# IsoJTAG.net
KiCad netlist of a schematic drawn in Altium Designer
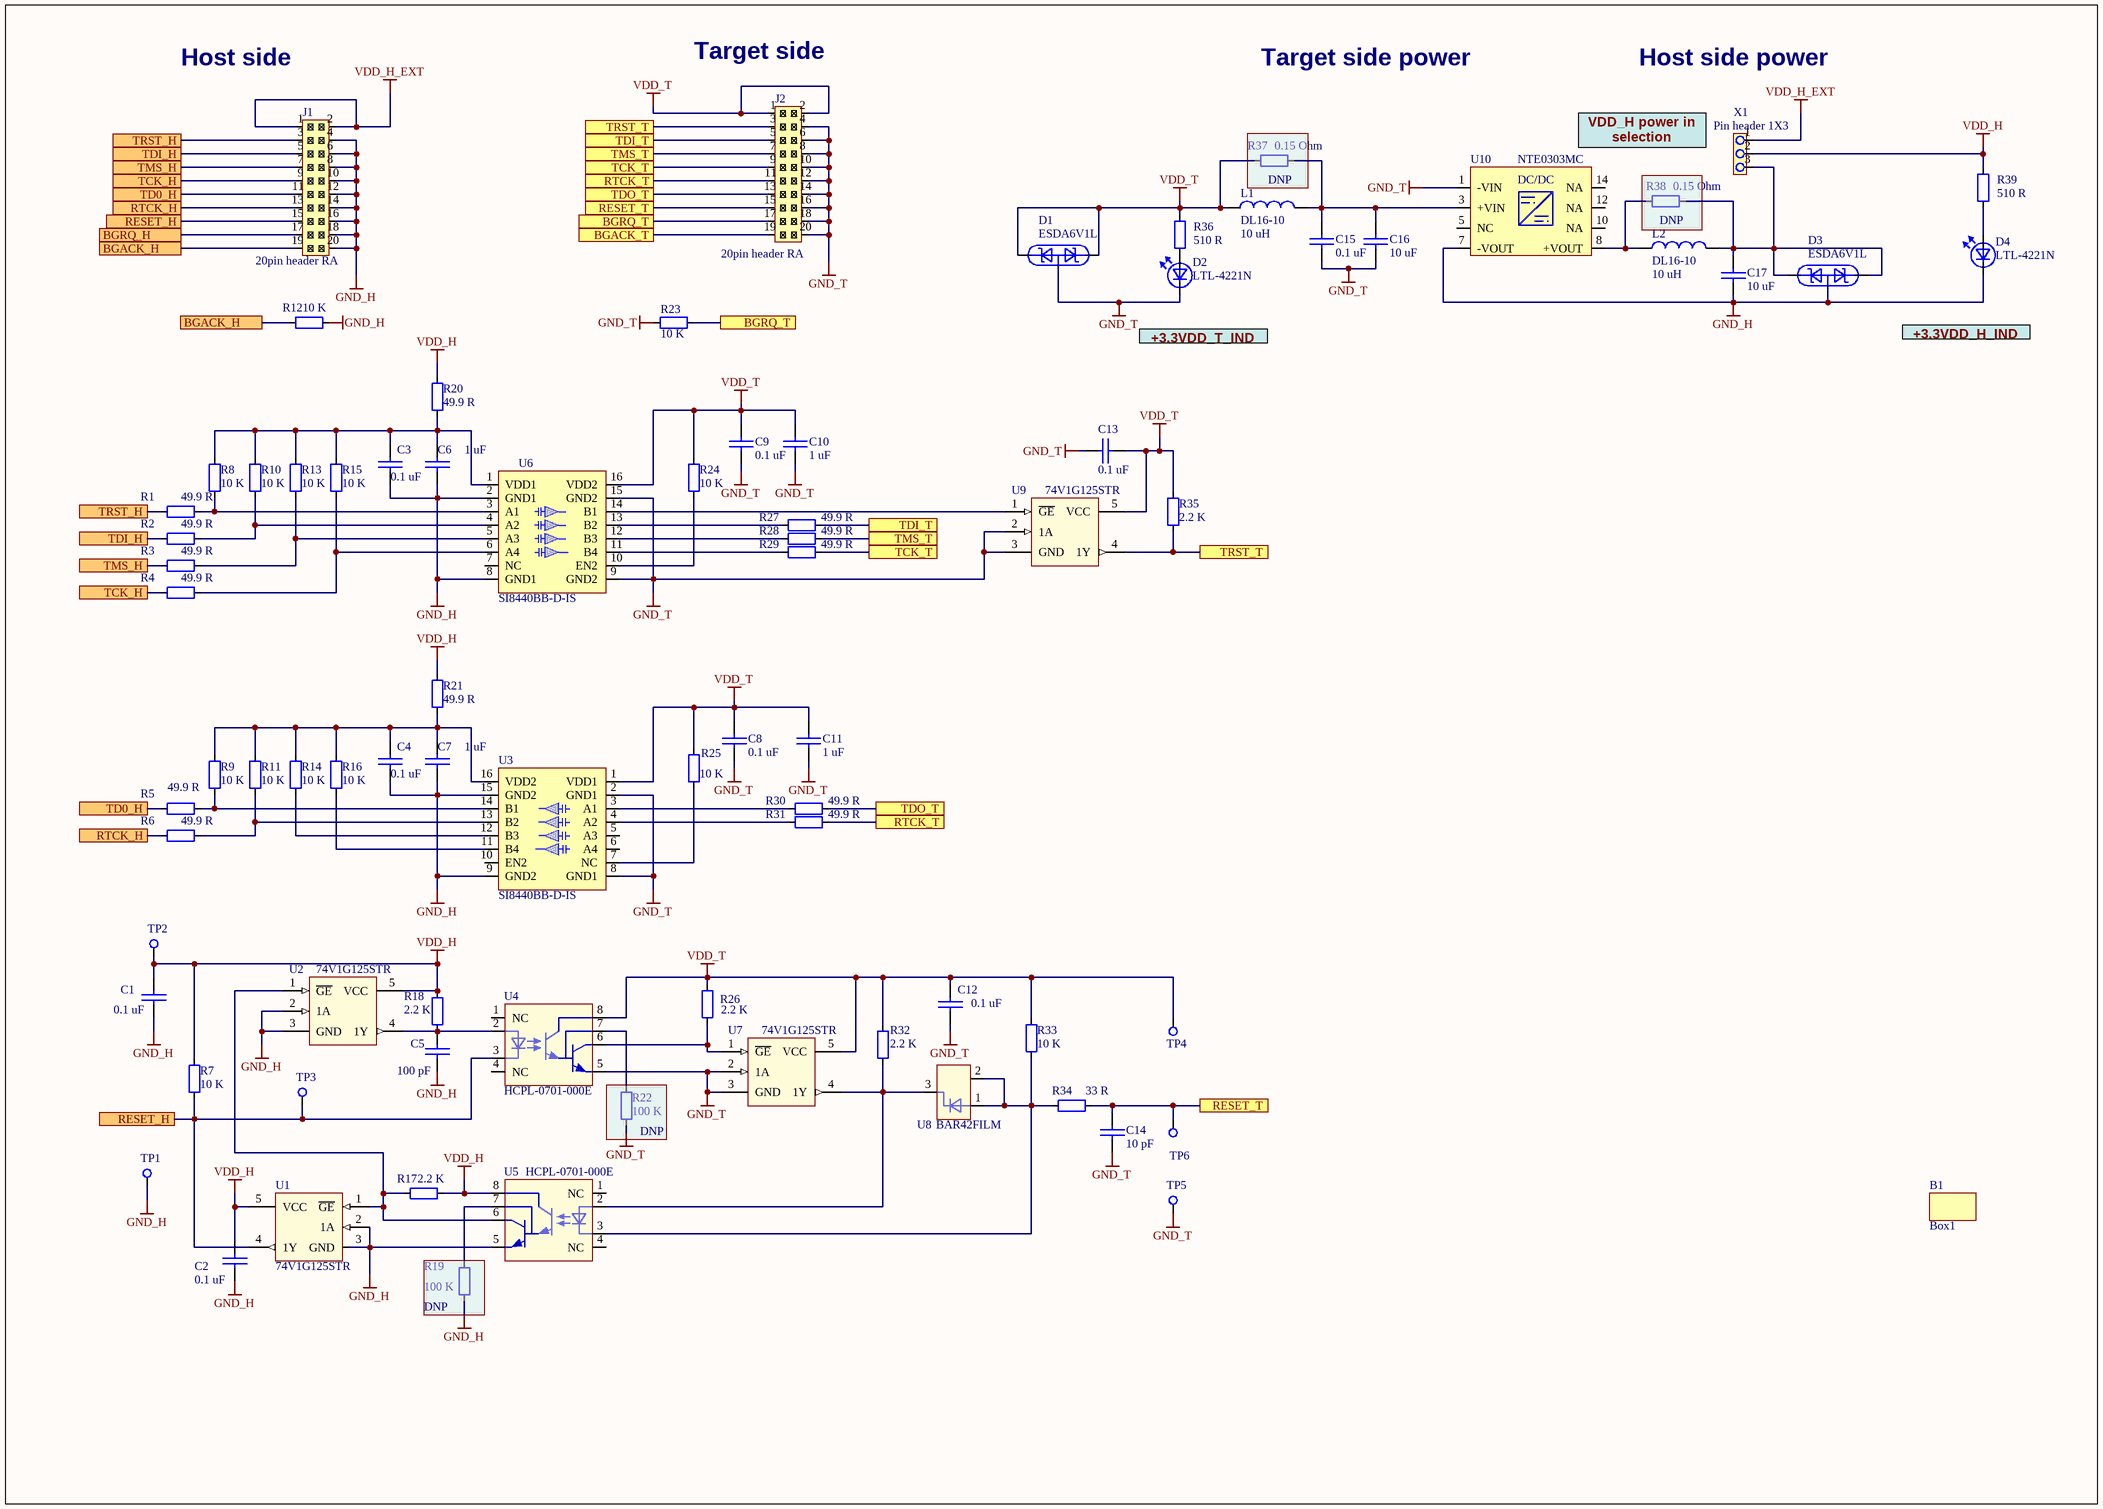
[diagram p0: IsoJTAG.SchDoc]

(export (version "E")
  (design (tool "Eeschema 10.0.6"))
  (components
    (comp (ref "B1")
      (value "Box1")
      (description "Enclosure: multipurpose; 1593; X:66mm; Y:66mm; Z:28mm; ABS; black")
      (fields (field (name "MANUFACTURER") "HAMMOND") (field (name "PARTNUM") "HA1593KBK"))
      (libsource (lib "JTAG_opto") (part "HA1593KBK box"))
    )
    (comp (ref "C1")
      (value "0.1 uF")
      (footprint "2012[0805]")
      (description "0.1 uF, X7R,  0805")
      (fields (field (name "VOLTAGE") "50 V") (field (name "TOLERANCE") "+-10%"))
      (libsource (lib "ea_Capacitors") (part "0805, 0.1 uF, 50 V, X7R"))
    )
    (comp (ref "C2")
      (value "0.1 uF")
      (footprint "2012[0805]")
      (description "0.1 uF, X7R,  0805")
      (fields (field (name "VOLTAGE") "50 V") (field (name "TOLERANCE") "+-10%"))
      (libsource (lib "ea_Capacitors") (part "0805, 0.1 uF, 50 V, X7R"))
    )
    (comp (ref "C3")
      (value "0.1 uF")
      (footprint "2012[0805]")
      (description "0.1 uF, X7R,  0805")
      (fields (field (name "VOLTAGE") "50 V") (field (name "TOLERANCE") "+-10%"))
      (libsource (lib "ea_Capacitors") (part "0805, 0.1 uF, 50 V, X7R"))
    )
    (comp (ref "C4")
      (value "0.1 uF")
      (footprint "2012[0805]")
      (description "0.1 uF, X7R,  0805")
      (fields (field (name "VOLTAGE") "50 V") (field (name "TOLERANCE") "+-10%"))
      (libsource (lib "ea_Capacitors") (part "0805, 0.1 uF, 50 V, X7R"))
    )
    (comp (ref "C5")
      (value "100 pF")
      (footprint "1608[0603]")
      (description "100 pF, 50V, 5%, NP0, 0603 SMD MLC Capacitor")
      (fields (field (name "VOLTAGE") "50 V") (field (name "TOLERANCE") "5%"))
      (libsource (lib "ea_Capacitors") (part "CCPF100K0603"))
    )
    (comp (ref "C6")
      (value "1 uF")
      (footprint "2012[0805]")
      (description "1 uF, 16V, 10%, X7R, 0805")
      (fields (field (name "VOLTAGE") "16 V") (field (name "TOLERANCE") "10%"))
      (libsource (lib "ea_Capacitors") (part "CVUF001K0805"))
    )
    (comp (ref "C7")
      (value "1 uF")
      (footprint "2012[0805]")
      (description "1 uF, 16V, 10%, X7R, 0805")
      (fields (field (name "VOLTAGE") "16 V") (field (name "TOLERANCE") "10%"))
      (libsource (lib "ea_Capacitors") (part "CVUF001K0805"))
    )
    (comp (ref "C8")
      (value "0.1 uF")
      (footprint "2012[0805]")
      (description "0.1 uF, X7R,  0805")
      (fields (field (name "VOLTAGE") "50 V") (field (name "TOLERANCE") "+-10%"))
      (libsource (lib "ea_Capacitors") (part "0805, 0.1 uF, 50 V, X7R"))
    )
    (comp (ref "C9")
      (value "0.1 uF")
      (footprint "2012[0805]")
      (description "0.1 uF, X7R,  0805")
      (fields (field (name "VOLTAGE") "50 V") (field (name "TOLERANCE") "+-10%"))
      (libsource (lib "ea_Capacitors") (part "0805, 0.1 uF, 50 V, X7R"))
    )
    (comp (ref "C10")
      (value "1 uF")
      (footprint "2012[0805]")
      (description "1 uF, 16V, 10%, X7R, 0805")
      (fields (field (name "VOLTAGE") "16 V") (field (name "TOLERANCE") "10%"))
      (libsource (lib "ea_Capacitors") (part "CVUF001K0805"))
    )
    (comp (ref "C11")
      (value "1 uF")
      (footprint "2012[0805]")
      (description "1 uF, 16V, 10%, X7R, 0805")
      (fields (field (name "VOLTAGE") "16 V") (field (name "TOLERANCE") "10%"))
      (libsource (lib "ea_Capacitors") (part "CVUF001K0805"))
    )
    (comp (ref "C12")
      (value "0.1 uF")
      (footprint "2012[0805]")
      (description "0.1 uF, X7R,  0805")
      (fields (field (name "VOLTAGE") "50 V") (field (name "TOLERANCE") "+-10%"))
      (libsource (lib "ea_Capacitors") (part "0805, 0.1 uF, 50 V, X7R"))
    )
    (comp (ref "C13")
      (value "0.1 uF")
      (footprint "2012[0805]")
      (description "0.1 uF, X7R,  0805")
      (fields (field (name "VOLTAGE") "50 V") (field (name "TOLERANCE") "+-10%"))
      (libsource (lib "ea_Capacitors") (part "0805, 0.1 uF, 50 V, X7R"))
    )
    (comp (ref "C14")
      (value "10 pF")
      (footprint "1608[0603]")
      (description "10 pF, 50V, 5%, NP0, 0603 SMD MLC Capacitor")
      (fields (field (name "VOLTAGE") "50 V") (field (name "TOLERANCE") "5%"))
      (libsource (lib "ea_Capacitors") (part "CCPF010K0603"))
    )
    (comp (ref "C15")
      (value "0.1 uF")
      (footprint "2012[0805]")
      (description "0.1 uF, X7R,  0805")
      (fields (field (name "VOLTAGE") "50 V") (field (name "TOLERANCE") "+-10%"))
      (libsource (lib "ea_Capacitors") (part "0805, 0.1 uF, 50 V, X7R"))
    )
    (comp (ref "C16")
      (value "10 uF")
      (footprint "2012[0805]")
      (description "10 uF, 10V, X5R, 10%, 0805,  -55°C..85°C")
      (fields (field (name "VOLTAGE") "10V") (field (name "TOLERANCE") "10%"))
      (libsource (lib "ea_Capacitors") (part "GRM21BR61A106KE19L"))
    )
    (comp (ref "C17")
      (value "10 uF")
      (footprint "2012[0805]")
      (description "10 uF, 10V, X5R, 10%, 0805,  -55°C..85°C")
      (fields (field (name "VOLTAGE") "10V") (field (name "TOLERANCE") "10%"))
      (libsource (lib "ea_Capacitors") (part "GRM21BR61A106KE19L"))
    )
    (comp (ref "D1")
      (value "ESDA6V1L")
      (footprint "SOT23")
      (description "Dual transil array for ESD, 6.1 V, 300 W")
      (fields (field (name "MANUFACTURER") "Micro Commercial Co") (field (name "PARTNUM") "ESDA6V1L-TPCT-ND"))
      (libsource (lib "*") (part "ESDA6V1L"))
    )
    (comp (ref "D2")
      (value "LTL-4221N")
      (footprint "LED 3 mm")
      (description "LED 3 mm")
      (libsource (lib "ea_Indicators") (part "LTL-4221N"))
    )
    (comp (ref "D3")
      (value "ESDA6V1L")
      (footprint "SOT23")
      (description "Dual transil array for ESD, 6.1 V, 300 W")
      (fields (field (name "MANUFACTURER") "Micro Commercial Co") (field (name "PARTNUM") "ESDA6V1L-TPCT-ND"))
      (libsource (lib "*") (part "ESDA6V1L"))
    )
    (comp (ref "D4")
      (value "LTL-4221N")
      (footprint "LED 3 mm")
      (description "LED 3 mm")
      (libsource (lib "ea_Indicators") (part "LTL-4221N"))
    )
    (comp (ref "J1")
      (value "20pin header RA")
      (footprint "918520x323")
      (description "Socket; IDC; male; PIN:20; angled; THT; 1.27mm; Pitch:2.54mm")
      (fields (field (name "MANUFACTURER") "Harting") (field (name "PARTNUM") "2-1634689-0"))
      (libsource (lib "JTAG_opto") (part "2-1634689-0 20pin header"))
    )
    (comp (ref "J2")
      (value "20pin header RA")
      (footprint "918520x323")
      (description "Socket; IDC; male; PIN:20; angled; THT; 1.27mm; Pitch:2.54mm")
      (fields (field (name "MANUFACTURER") "Harting") (field (name "PARTNUM") "2-1634689-0"))
      (libsource (lib "JTAG_opto") (part "2-1634689-0 20pin header"))
    )
    (comp (ref "L1")
      (value "DL16-10")
      (footprint "DL16-10")
      (description "Inductor: wire; 10uH; Ioper:1.1A; 0.16R; SMD; Isat:1.1A; B:4.45mm")
      (fields
        (field (name "MANUFACTURER") "FERROCORE")
        (field (name "TOLERANCE") "20%")
        (field (name "ALTIUM_VALUE") "10 uH")
      )
      (libsource (lib "JTAG_opto") (part "DL16-10 10uH"))
    )
    (comp (ref "L2")
      (value "DL16-10")
      (footprint "DL16-10")
      (description "Inductor: wire; 10uH; Ioper:1.1A; 0.16R; SMD; Isat:1.1A; B:4.45mm")
      (fields
        (field (name "MANUFACTURER") "FERROCORE")
        (field (name "TOLERANCE") "20%")
        (field (name "ALTIUM_VALUE") "10 uH")
      )
      (libsource (lib "JTAG_opto") (part "DL16-10 10uH"))
    )
    (comp (ref "R1")
      (value "49.9 R")
      (footprint "0603")
      (description "49.9 R, 1%, 0.1 W, 0603, SMD Resistor, Taped")
      (fields (field (name "MANUFACTURER") "Vishay/Dale") (field (name "TOLERANCE") "1%"))
      (libsource (lib "ea_Resistors") (part "CRCW060349R9FKEA"))
    )
    (comp (ref "R2")
      (value "49.9 R")
      (footprint "0603")
      (description "49.9 R, 1%, 0.1 W, 0603, SMD Resistor, Taped")
      (fields (field (name "MANUFACTURER") "Vishay/Dale") (field (name "TOLERANCE") "1%"))
      (libsource (lib "ea_Resistors") (part "CRCW060349R9FKEA"))
    )
    (comp (ref "R3")
      (value "49.9 R")
      (footprint "0603")
      (description "49.9 R, 1%, 0.1 W, 0603, SMD Resistor, Taped")
      (fields (field (name "MANUFACTURER") "Vishay/Dale") (field (name "TOLERANCE") "1%"))
      (libsource (lib "ea_Resistors") (part "CRCW060349R9FKEA"))
    )
    (comp (ref "R4")
      (value "49.9 R")
      (footprint "0603")
      (description "49.9 R, 1%, 0.1 W, 0603, SMD Resistor, Taped")
      (fields (field (name "MANUFACTURER") "Vishay/Dale") (field (name "TOLERANCE") "1%"))
      (libsource (lib "ea_Resistors") (part "CRCW060349R9FKEA"))
    )
    (comp (ref "R5")
      (value "49.9 R")
      (footprint "0603")
      (description "49.9 R, 1%, 0.1 W, 0603, SMD Resistor, Taped")
      (fields (field (name "MANUFACTURER") "Vishay/Dale") (field (name "TOLERANCE") "1%"))
      (libsource (lib "ea_Resistors") (part "CRCW060349R9FKEA"))
    )
    (comp (ref "R6")
      (value "49.9 R")
      (footprint "0603")
      (description "49.9 R, 1%, 0.1 W, 0603, SMD Resistor, Taped")
      (fields (field (name "MANUFACTURER") "Vishay/Dale") (field (name "TOLERANCE") "1%"))
      (libsource (lib "ea_Resistors") (part "CRCW060349R9FKEA"))
    )
    (comp (ref "R7")
      (value "10 K")
      (footprint "0603")
      (description "10 K, 1%, 0603, SMD Resistor, Taped")
      (fields (field (name "MANUFACTURER") "Vishay") (field (name "TOLERANCE") "1%"))
      (libsource (lib "ea_Resistors") (part "RL0603K010-1"))
    )
    (comp (ref "R8")
      (value "10 K")
      (footprint "0603")
      (description "10 K, 1%, 0603, SMD Resistor, Taped")
      (fields (field (name "MANUFACTURER") "Vishay") (field (name "TOLERANCE") "1%"))
      (libsource (lib "ea_Resistors") (part "RL0603K010-1"))
    )
    (comp (ref "R9")
      (value "10 K")
      (footprint "0603")
      (description "10 K, 1%, 0603, SMD Resistor, Taped")
      (fields (field (name "MANUFACTURER") "Vishay") (field (name "TOLERANCE") "1%"))
      (libsource (lib "ea_Resistors") (part "RL0603K010-1"))
    )
    (comp (ref "R10")
      (value "10 K")
      (footprint "0603")
      (description "10 K, 1%, 0603, SMD Resistor, Taped")
      (fields (field (name "MANUFACTURER") "Vishay") (field (name "TOLERANCE") "1%"))
      (libsource (lib "ea_Resistors") (part "RL0603K010-1"))
    )
    (comp (ref "R11")
      (value "10 K")
      (footprint "0603")
      (description "10 K, 1%, 0603, SMD Resistor, Taped")
      (fields (field (name "MANUFACTURER") "Vishay") (field (name "TOLERANCE") "1%"))
      (libsource (lib "ea_Resistors") (part "RL0603K010-1"))
    )
    (comp (ref "R12")
      (value "10 K")
      (footprint "0603")
      (description "10 K, 1%, 0603, SMD Resistor, Taped")
      (fields (field (name "MANUFACTURER") "Vishay") (field (name "TOLERANCE") "1%"))
      (libsource (lib "") (part "RL0603K010-1_1"))
    )
    (comp (ref "R13")
      (value "10 K")
      (footprint "0603")
      (description "10 K, 1%, 0603, SMD Resistor, Taped")
      (fields (field (name "MANUFACTURER") "Vishay") (field (name "TOLERANCE") "1%"))
      (libsource (lib "ea_Resistors") (part "RL0603K010-1"))
    )
    (comp (ref "R14")
      (value "10 K")
      (footprint "0603")
      (description "10 K, 1%, 0603, SMD Resistor, Taped")
      (fields (field (name "MANUFACTURER") "Vishay") (field (name "TOLERANCE") "1%"))
      (libsource (lib "ea_Resistors") (part "RL0603K010-1"))
    )
    (comp (ref "R15")
      (value "10 K")
      (footprint "0603")
      (description "10 K, 1%, 0603, SMD Resistor, Taped")
      (fields (field (name "MANUFACTURER") "Vishay") (field (name "TOLERANCE") "1%"))
      (libsource (lib "ea_Resistors") (part "RL0603K010-1"))
    )
    (comp (ref "R16")
      (value "10 K")
      (footprint "0603")
      (description "10 K, 1%, 0603, SMD Resistor, Taped")
      (fields (field (name "MANUFACTURER") "Vishay") (field (name "TOLERANCE") "1%"))
      (libsource (lib "ea_Resistors") (part "RL0603K010-1"))
    )
    (comp (ref "R17")
      (value "2.2 K")
      (footprint "0603")
      (description "2.2 K, 1%, 0603, SMD Resistor, Taped")
      (fields (field (name "MANUFACTURER") "Vishay") (field (name "TOLERANCE") "1%"))
      (libsource (lib "") (part "RL0603K002.2-1_1"))
    )
    (comp (ref "R18")
      (value "2.2 K")
      (footprint "0603")
      (description "2.2 K, 1%, 0603, SMD Resistor, Taped")
      (fields (field (name "MANUFACTURER") "Vishay") (field (name "TOLERANCE") "1%"))
      (libsource (lib "ea_Resistors") (part "RL0603K002.2-1"))
    )
    (comp (ref "R19")
      (value "100 K")
      (footprint "0603")
      (description "100 K, 1%, 0603, SMD Resistor, Taped")
      (fields (field (name "MANUFACTURER") "Vishay") (field (name "TOLERANCE") "1%"))
      (libsource (lib "ea_Resistors") (part "RL0603K100-1"))
    )
    (comp (ref "R20")
      (value "49.9 R")
      (footprint "0603")
      (description "49.9 R, 1%, 0.1 W, 0603, SMD Resistor, Taped")
      (fields (field (name "MANUFACTURER") "Vishay/Dale") (field (name "TOLERANCE") "1%"))
      (libsource (lib "") (part "CRCW060349R9FKEA_1"))
    )
    (comp (ref "R21")
      (value "49.9 R")
      (footprint "0603")
      (description "49.9 R, 1%, 0.1 W, 0603, SMD Resistor, Taped")
      (fields (field (name "MANUFACTURER") "Vishay/Dale") (field (name "TOLERANCE") "1%"))
      (libsource (lib "") (part "CRCW060349R9FKEA_1"))
    )
    (comp (ref "R22")
      (value "100 K")
      (footprint "0603")
      (description "100 K, 1%, 0603, SMD Resistor, Taped")
      (fields (field (name "MANUFACTURER") "Vishay") (field (name "TOLERANCE") "1%"))
      (libsource (lib "") (part "RL0603K100-1_1"))
    )
    (comp (ref "R23")
      (value "10 K")
      (footprint "0603")
      (description "10 K, 1%, 0603, SMD Resistor, Taped")
      (fields (field (name "MANUFACTURER") "Vishay") (field (name "TOLERANCE") "1%"))
      (libsource (lib "ea_Resistors") (part "RL0603K010-1"))
    )
    (comp (ref "R24")
      (value "10 K")
      (footprint "0603")
      (description "10 K, 1%, 0603, SMD Resistor, Taped")
      (fields (field (name "MANUFACTURER") "Vishay") (field (name "TOLERANCE") "1%"))
      (libsource (lib "") (part "RL0603K010-1_2"))
    )
    (comp (ref "R25")
      (value "10 K")
      (footprint "0603")
      (description "10 K, 1%, 0603, SMD Resistor, Taped")
      (fields (field (name "MANUFACTURER") "Vishay") (field (name "TOLERANCE") "1%"))
      (libsource (lib "") (part "RL0603K010-1_2"))
    )
    (comp (ref "R26")
      (value "2.2 K")
      (footprint "0603")
      (description "2.2 K, 1%, 0603, SMD Resistor, Taped")
      (fields (field (name "MANUFACTURER") "Vishay") (field (name "TOLERANCE") "1%"))
      (libsource (lib "ea_Resistors") (part "RL0603K002.2-1"))
    )
    (comp (ref "R27")
      (value "49.9 R")
      (footprint "0603")
      (description "49.9 R, 1%, 0.1 W, 0603, SMD Resistor, Taped")
      (fields (field (name "MANUFACTURER") "Vishay/Dale") (field (name "TOLERANCE") "1%"))
      (libsource (lib "ea_Resistors") (part "CRCW060349R9FKEA"))
    )
    (comp (ref "R28")
      (value "49.9 R")
      (footprint "0603")
      (description "49.9 R, 1%, 0.1 W, 0603, SMD Resistor, Taped")
      (fields (field (name "MANUFACTURER") "Vishay/Dale") (field (name "TOLERANCE") "1%"))
      (libsource (lib "ea_Resistors") (part "CRCW060349R9FKEA"))
    )
    (comp (ref "R29")
      (value "49.9 R")
      (footprint "0603")
      (description "49.9 R, 1%, 0.1 W, 0603, SMD Resistor, Taped")
      (fields (field (name "MANUFACTURER") "Vishay/Dale") (field (name "TOLERANCE") "1%"))
      (libsource (lib "ea_Resistors") (part "CRCW060349R9FKEA"))
    )
    (comp (ref "R30")
      (value "49.9 R")
      (footprint "0603")
      (description "49.9 R, 1%, 0.1 W, 0603, SMD Resistor, Taped")
      (fields (field (name "MANUFACTURER") "Vishay/Dale") (field (name "TOLERANCE") "1%"))
      (libsource (lib "ea_Resistors") (part "CRCW060349R9FKEA"))
    )
    (comp (ref "R31")
      (value "49.9 R")
      (footprint "0603")
      (description "49.9 R, 1%, 0.1 W, 0603, SMD Resistor, Taped")
      (fields (field (name "MANUFACTURER") "Vishay/Dale") (field (name "TOLERANCE") "1%"))
      (libsource (lib "ea_Resistors") (part "CRCW060349R9FKEA"))
    )
    (comp (ref "R32")
      (value "2.2 K")
      (footprint "0603")
      (description "2.2 K, 1%, 0603, SMD Resistor, Taped")
      (fields (field (name "MANUFACTURER") "Vishay") (field (name "TOLERANCE") "1%"))
      (libsource (lib "ea_Resistors") (part "RL0603K002.2-1"))
    )
    (comp (ref "R33")
      (value "10 K")
      (footprint "0603")
      (description "10 K, 1%, 0603, SMD Resistor, Taped")
      (fields (field (name "MANUFACTURER") "Vishay") (field (name "TOLERANCE") "1%"))
      (libsource (lib "ea_Resistors") (part "RL0603K010-1"))
    )
    (comp (ref "R34")
      (value "33 R")
      (footprint "0603")
      (description "33 R, 1%, 0603, SMD Resistor, Taped")
      (fields (field (name "MANUFACTURER") "Vishay") (field (name "TOLERANCE") "1%"))
      (libsource (lib "ea_Resistors") (part "RL0603E033-1"))
    )
    (comp (ref "R35")
      (value "2.2 K")
      (footprint "0603")
      (description "2.2 K, 1%, 0603, SMD Resistor, Taped")
      (fields (field (name "MANUFACTURER") "Vishay") (field (name "TOLERANCE") "1%"))
      (libsource (lib "ea_Resistors") (part "RL0603K002.2-1"))
    )
    (comp (ref "R36")
      (value "510 R")
      (footprint "0603")
      (description "510 R, 1%, 0603, SMD Resistor, Taped")
      (fields (field (name "MANUFACTURER") "Vishay") (field (name "TOLERANCE") "1%"))
      (libsource (lib "ea_Resistors") (part "RL0603E510-1"))
    )
    (comp (ref "R37")
      (value "0.15 Ohm")
      (footprint "3216[1206]")
      (description "0.15 Ohm, 0.25 W, 1% 1206")
      (fields (field (name "MANUFACTURER") "Panasonic") (field (name "TOLERANCE") "1%"))
      (libsource (lib "ea_Resistors") (part "ERJ-8RSFR15V"))
    )
    (comp (ref "R38")
      (value "0.15 Ohm")
      (footprint "3216[1206]")
      (description "0.15 Ohm, 0.25 W, 1% 1206")
      (fields (field (name "MANUFACTURER") "Panasonic") (field (name "TOLERANCE") "1%"))
      (libsource (lib "ea_Resistors") (part "ERJ-8RSFR15V"))
    )
    (comp (ref "R39")
      (value "510 R")
      (footprint "0603")
      (description "510 R, 1%, 0603, SMD Resistor, Taped")
      (fields (field (name "MANUFACTURER") "Vishay") (field (name "TOLERANCE") "1%"))
      (libsource (lib "ea_Resistors") (part "RL0603E510-1"))
    )
    (comp (ref "TP1")
      (value "TP 0.4-0.8")
      (footprint "TP 0.4-0.8")
      (libsource (lib "ea_Mechanical") (part "TP 0.4-0.8"))
    )
    (comp (ref "TP2")
      (value "TP 0.4-0.8")
      (footprint "TP 0.4-0.8")
      (libsource (lib "ea_Mechanical") (part "TP 0.4-0.8"))
    )
    (comp (ref "TP3")
      (value "TP 0.4-0.8")
      (footprint "TP 0.4-0.8")
      (libsource (lib "ea_Mechanical") (part "TP 0.4-0.8"))
    )
    (comp (ref "TP4")
      (value "TP 0.4-0.8")
      (footprint "TP 0.4-0.8")
      (libsource (lib "ea_Mechanical") (part "TP 0.4-0.8"))
    )
    (comp (ref "TP5")
      (value "TP 0.4-0.8")
      (footprint "TP 0.4-0.8")
      (libsource (lib "ea_Mechanical") (part "TP 0.4-0.8"))
    )
    (comp (ref "TP6")
      (value "TP 0.4-0.8")
      (footprint "TP 0.4-0.8")
      (libsource (lib "ea_Mechanical") (part "TP 0.4-0.8"))
    )
    (comp (ref "U1")
      (value "74V1G125STR")
      (footprint "SOT23-5L")
      (description "Single Bus Buffer (3-State), Non Inverting, 2-5.5V, SOT-23-5, -55-125C,")
      (fields (field (name "MANUFACTURER") "ST"))
      (libsource (lib "") (part "74V1G125STR buffer_1"))
    )
    (comp (ref "U2")
      (value "74V1G125STR")
      (footprint "SOT23-5L")
      (description "Single Bus Buffer (3-State), Non Inverting, 2-5.5V, SOT-23-5, -55-125C,")
      (fields (field (name "MANUFACTURER") "ST"))
      (libsource (lib "ea_IC_registers_buffers") (part "74V1G125STR buffer"))
    )
    (comp (ref "U3")
      (value "SI8440BB-D-IS")
      (footprint "SO-G16/D10.4")
      (description "IC ISOLATOR 4CH 5.5V 16-SOIC")
      (fields
        (field (name "MANUFACTURER") "Silicon Laboratories Inc")
        (field (name "PARTNUM") "336-1760-5-ND")
      )
      (libsource (lib "") (part "SI8440AB-D-IS_1"))
    )
    (comp (ref "U4")
      (value "HCPL-0701-000E")
      (footprint "SO-8")
      (description "OPTOCOUPLER, SMD, TRANSISTOR O/P")
      (fields (field (name "MANUFACTURER") "Avago"))
      (libsource (lib "ea_Opto") (part "HCPL-0701-000E"))
    )
    (comp (ref "U5")
      (value "HCPL-0701-000E")
      (footprint "SO-8")
      (description "OPTOCOUPLER, SMD, TRANSISTOR O/P")
      (fields (field (name "MANUFACTURER") "Avago"))
      (libsource (lib "") (part "HCPL-0701-000E_1"))
    )
    (comp (ref "U6")
      (value "SI8440BB-D-IS")
      (footprint "SO-G16/D10.4")
      (description "IC ISOLATOR 4CH 5.5V 16-SOIC")
      (fields
        (field (name "MANUFACTURER") "Silicon Laboratories Inc")
        (field (name "PARTNUM") "336-1760-5-ND")
      )
      (libsource (lib "ea_IC_Interfaces") (part "SI8440AB-D-IS"))
    )
    (comp (ref "U7")
      (value "74V1G125STR")
      (footprint "SOT23-5L")
      (description "Single Bus Buffer (3-State), Non Inverting, 2-5.5V, SOT-23-5, -55-125C,")
      (fields (field (name "MANUFACTURER") "ST"))
      (libsource (lib "ea_IC_registers_buffers") (part "74V1G125STR buffer"))
    )
    (comp (ref "U8")
      (value "BAR42FILM")
      (footprint "SOT23")
      (description "Schottky Single 30V, 100 mA, 400mV, SOT-23, Marking D94")
      (fields (field (name "MANUFACTURER") "ST"))
      (libsource (lib "ea_Diodes") (part "BAR42FILM"))
    )
    (comp (ref "U9")
      (value "74V1G125STR")
      (footprint "SOT23-5L")
      (description "Single Bus Buffer (3-State), Non Inverting, 2-5.5V, SOT-23-5, -55-125C,")
      (fields (field (name "MANUFACTURER") "ST"))
      (libsource (lib "ea_IC_registers_buffers") (part "74V1G125STR buffer"))
    )
    (comp (ref "U10")
      (value "NTE0303MC")
      (footprint "NTE DC_DC")
      (description "CONVERTER, DC/DC, SMD, 1W, 3.3V,  12,7x6.6x7.7mm, 1kV isol")
      (fields (field (name "MANUFACTURER") "MURATA"))
      (libsource (lib "JTAG_opto") (part "NTE0303MC DC/DC"))
    )
    (comp (ref "X1")
      (value "Pin header 1X3")
      (footprint "HDR1X3")
      (libsource (lib "ea_Connectors") (part "Pin header 1X3"))
    )
  )
  (nets
    (net (code "1") (name "/BGACK_H") (class "Default")
      (node (ref "J1") (pin "19") (pinfunction "19_19") (pintype "passive"))
      (node (ref "R12") (pin "2") (pinfunction "2_2") (pintype "passive"))
    )
    (net (code "2") (name "/BGACK_T") (class "Default")
      (node (ref "J2") (pin "19") (pinfunction "19_19") (pintype "passive"))
    )
    (net (code "3") (name "/BGRQ_H") (class "Default")
      (node (ref "J1") (pin "17") (pinfunction "17_17") (pintype "passive"))
    )
    (net (code "4") (name "/BGRQ_T") (class "Default")
      (node (ref "J2") (pin "17") (pinfunction "17_17") (pintype "passive"))
      (node (ref "R23") (pin "2") (pinfunction "2_2") (pintype "passive"))
    )
    (net (code "5") (name "/RESET_H") (class "Default")
      (node (ref "J1") (pin "15") (pinfunction "15_15") (pintype "passive"))
      (node (ref "R7") (pin "1") (pinfunction "1_1") (pintype "passive"))
      (node (ref "TP3") (pin "1") (pinfunction "1_1") (pintype "passive"))
      (node (ref "U1") (pin "4") (pinfunction "1Y_4") (pintype "output"))
      (node (ref "U4") (pin "3") (pinfunction "C_3") (pintype "passive"))
    )
    (net (code "6") (name "/RESET_T") (class "Default")
      (node (ref "C14") (pin "1") (pinfunction "1_1") (pintype "passive"))
      (node (ref "J2") (pin "15") (pinfunction "15_15") (pintype "passive"))
      (node (ref "R34") (pin "1") (pinfunction "1_1") (pintype "passive"))
      (node (ref "TP6") (pin "1") (pinfunction "1_1") (pintype "passive"))
    )
    (net (code "7") (name "/RTCK_H") (class "Default")
      (node (ref "J1") (pin "13") (pinfunction "13_13") (pintype "passive"))
      (node (ref "R6") (pin "2") (pinfunction "2_2") (pintype "passive"))
    )
    (net (code "8") (name "/RTCK_T") (class "Default")
      (node (ref "J2") (pin "11") (pinfunction "11_11") (pintype "passive"))
      (node (ref "R31") (pin "1") (pinfunction "1_1") (pintype "passive"))
    )
    (net (code "9") (name "/TCK_H") (class "Default")
      (node (ref "J1") (pin "9") (pinfunction "9_9") (pintype "passive"))
      (node (ref "R4") (pin "2") (pinfunction "2_2") (pintype "passive"))
    )
    (net (code "10") (name "/TCK_T") (class "Default")
      (node (ref "J2") (pin "9") (pinfunction "9_9") (pintype "passive"))
      (node (ref "R29") (pin "1") (pinfunction "1_1") (pintype "passive"))
    )
    (net (code "11") (name "/TD0_H") (class "Default")
      (node (ref "J1") (pin "11") (pinfunction "11_11") (pintype "passive"))
      (node (ref "R5") (pin "2") (pinfunction "2_2") (pintype "passive"))
    )
    (net (code "12") (name "/TDI_H") (class "Default")
      (node (ref "J1") (pin "5") (pinfunction "5_5") (pintype "passive"))
      (node (ref "R2") (pin "2") (pinfunction "2_2") (pintype "passive"))
    )
    (net (code "13") (name "/TDI_T") (class "Default")
      (node (ref "J2") (pin "5") (pinfunction "5_5") (pintype "passive"))
      (node (ref "R27") (pin "1") (pinfunction "1_1") (pintype "passive"))
    )
    (net (code "14") (name "/TDO_T") (class "Default")
      (node (ref "J2") (pin "13") (pinfunction "13_13") (pintype "passive"))
      (node (ref "R30") (pin "1") (pinfunction "1_1") (pintype "passive"))
    )
    (net (code "15") (name "/TMS_H") (class "Default")
      (node (ref "J1") (pin "7") (pinfunction "7_7") (pintype "passive"))
      (node (ref "R3") (pin "2") (pinfunction "2_2") (pintype "passive"))
    )
    (net (code "16") (name "/TMS_T") (class "Default")
      (node (ref "J2") (pin "7") (pinfunction "7_7") (pintype "passive"))
      (node (ref "R28") (pin "1") (pinfunction "1_1") (pintype "passive"))
    )
    (net (code "17") (name "/TRST_H") (class "Default")
      (node (ref "J1") (pin "3") (pinfunction "3_3") (pintype "passive"))
      (node (ref "R1") (pin "2") (pinfunction "2_2") (pintype "passive"))
    )
    (net (code "18") (name "/TRST_T") (class "Default")
      (node (ref "J2") (pin "3") (pinfunction "3_3") (pintype "passive"))
      (node (ref "R35") (pin "1") (pinfunction "1_1") (pintype "passive"))
      (node (ref "U9") (pin "4") (pinfunction "1Y_4") (pintype "output"))
    )
    (net (code "19") (name "GND_H") (class "Default")
      (node (ref "C1") (pin "2") (pinfunction "2_2") (pintype "passive"))
      (node (ref "C17") (pin "2") (pinfunction "2_2") (pintype "passive"))
      (node (ref "C2") (pin "2") (pinfunction "2_2") (pintype "passive"))
      (node (ref "C3") (pin "1") (pinfunction "1_1") (pintype "passive"))
      (node (ref "C4") (pin "1") (pinfunction "1_1") (pintype "passive"))
      (node (ref "C5") (pin "2") (pinfunction "2_2") (pintype "passive"))
      (node (ref "C6") (pin "2") (pinfunction "2_2") (pintype "passive"))
      (node (ref "C7") (pin "2") (pinfunction "2_2") (pintype "passive"))
      (node (ref "D3") (pin "3") (pintype "passive"))
      (node (ref "D4") (pin "1") (pinfunction "C_1") (pintype "passive"))
      (node (ref "J1") (pin "10") (pinfunction "10_10") (pintype "passive"))
      (node (ref "J1") (pin "12") (pinfunction "12_12") (pintype "passive"))
      (node (ref "J1") (pin "14") (pinfunction "14_14") (pintype "passive"))
      (node (ref "J1") (pin "16") (pinfunction "16_16") (pintype "passive"))
      (node (ref "J1") (pin "18") (pinfunction "18_18") (pintype "passive"))
      (node (ref "J1") (pin "20") (pinfunction "20_20") (pintype "passive"))
      (node (ref "J1") (pin "4") (pinfunction "4_4") (pintype "passive"))
      (node (ref "J1") (pin "6") (pinfunction "6_6") (pintype "passive"))
      (node (ref "J1") (pin "8") (pinfunction "8_8") (pintype "passive"))
      (node (ref "R12") (pin "1") (pinfunction "1_1") (pintype "passive"))
      (node (ref "R19") (pin "2") (pinfunction "2_2") (pintype "passive"))
      (node (ref "TP1") (pin "1") (pinfunction "1_1") (pintype "passive"))
      (node (ref "U1") (pin "2") (pinfunction "1A_2") (pintype "input"))
      (node (ref "U1") (pin "3") (pinfunction "GND_3") (pintype "passive"))
      (node (ref "U10") (pin "7") (pinfunction "-VOUT_7") (pintype "passive"))
      (node (ref "U2") (pin "2") (pinfunction "1A_2") (pintype "input"))
      (node (ref "U2") (pin "3") (pinfunction "GND_3") (pintype "passive"))
      (node (ref "U3") (pin "15") (pinfunction "GND2_15") (pintype "passive"))
      (node (ref "U3") (pin "9") (pinfunction "GND2_9") (pintype "passive"))
      (node (ref "U5") (pin "5") (pinfunction "C_5") (pintype "passive"))
      (node (ref "U6") (pin "2") (pinfunction "GND1_2") (pintype "passive"))
      (node (ref "U6") (pin "8") (pinfunction "GND1_8") (pintype "passive"))
    )
    (net (code "20") (name "GND_T") (class "Default")
      (node (ref "C10") (pin "2") (pinfunction "2_2") (pintype "passive"))
      (node (ref "C11") (pin "2") (pinfunction "2_2") (pintype "passive"))
      (node (ref "C12") (pin "2") (pinfunction "2_2") (pintype "passive"))
      (node (ref "C13") (pin "1") (pinfunction "1_1") (pintype "passive"))
      (node (ref "C14") (pin "2") (pinfunction "2_2") (pintype "passive"))
      (node (ref "C15") (pin "1") (pinfunction "1_1") (pintype "passive"))
      (node (ref "C16") (pin "1") (pinfunction "1_1") (pintype "passive"))
      (node (ref "C8") (pin "1") (pinfunction "1_1") (pintype "passive"))
      (node (ref "C9") (pin "1") (pinfunction "1_1") (pintype "passive"))
      (node (ref "D1") (pin "3") (pintype "passive"))
      (node (ref "D2") (pin "1") (pinfunction "C_1") (pintype "passive"))
      (node (ref "J2") (pin "10") (pinfunction "10_10") (pintype "passive"))
      (node (ref "J2") (pin "12") (pinfunction "12_12") (pintype "passive"))
      (node (ref "J2") (pin "14") (pinfunction "14_14") (pintype "passive"))
      (node (ref "J2") (pin "16") (pinfunction "16_16") (pintype "passive"))
      (node (ref "J2") (pin "18") (pinfunction "18_18") (pintype "passive"))
      (node (ref "J2") (pin "20") (pinfunction "20_20") (pintype "passive"))
      (node (ref "J2") (pin "4") (pinfunction "4_4") (pintype "passive"))
      (node (ref "J2") (pin "6") (pinfunction "6_6") (pintype "passive"))
      (node (ref "J2") (pin "8") (pinfunction "8_8") (pintype "passive"))
      (node (ref "R22") (pin "1") (pinfunction "1_1") (pintype "passive"))
      (node (ref "R23") (pin "1") (pinfunction "1_1") (pintype "passive"))
      (node (ref "TP5") (pin "1") (pinfunction "1_1") (pintype "passive"))
      (node (ref "U10") (pin "1") (pinfunction "-VIN_1") (pintype "passive"))
      (node (ref "U3") (pin "2") (pinfunction "GND1_2") (pintype "passive"))
      (node (ref "U3") (pin "8") (pinfunction "GND1_8") (pintype "passive"))
      (node (ref "U4") (pin "5") (pinfunction "C_5") (pintype "passive"))
      (node (ref "U6") (pin "15") (pinfunction "GND2_15") (pintype "passive"))
      (node (ref "U6") (pin "9") (pinfunction "GND2_9") (pintype "passive"))
      (node (ref "U7") (pin "2") (pinfunction "1A_2") (pintype "input"))
      (node (ref "U7") (pin "3") (pinfunction "GND_3") (pintype "passive"))
      (node (ref "U9") (pin "2") (pinfunction "1A_2") (pintype "input"))
      (node (ref "U9") (pin "3") (pinfunction "GND_3") (pintype "passive"))
    )
    (net (code "21") (name "Net-(C17-Pad1)") (class "Default")
      (node (ref "C17") (pin "1") (pinfunction "1_1") (pintype "passive"))
      (node (ref "D3") (pin "1") (pintype "passive"))
      (node (ref "D3") (pin "2") (pintype "passive"))
      (node (ref "L2") (pin "2") (pinfunction "2_2") (pintype "passive"))
      (node (ref "R38") (pin "1") (pinfunction "1_1") (pintype "passive"))
      (node (ref "X1") (pin "3") (pinfunction "3_3") (pintype "passive"))
    )
    (net (code "22") (name "Net-(D2-A)") (class "Default")
      (node (ref "D2") (pin "2") (pinfunction "A_2") (pintype "passive"))
      (node (ref "R36") (pin "1") (pinfunction "1_1") (pintype "passive"))
    )
    (net (code "23") (name "Net-(D4-A)") (class "Default")
      (node (ref "D4") (pin "2") (pinfunction "A_2") (pintype "passive"))
      (node (ref "R39") (pin "1") (pinfunction "1_1") (pintype "passive"))
    )
    (net (code "24") (name "Net-(R19-Pad1)") (class "Default")
      (node (ref "R19") (pin "1") (pinfunction "1_1") (pintype "passive"))
      (node (ref "U5") (pin "7") (pinfunction "C_7") (pintype "passive"))
    )
    (net (code "25") (name "Net-(R22-Pad2)") (class "Default")
      (node (ref "R22") (pin "2") (pinfunction "2_2") (pintype "passive"))
      (node (ref "U4") (pin "7") (pinfunction "C_7") (pintype "passive"))
    )
    (net (code "26") (name "Net-(U1-~{GE})") (class "Default")
      (node (ref "R17") (pin "2") (pinfunction "2_2") (pintype "passive"))
      (node (ref "U1") (pin "1") (pinfunction "~{GE}_1") (pintype "input"))
      (node (ref "U2") (pin "1") (pinfunction "~{GE}_1") (pintype "input"))
      (node (ref "U5") (pin "6") (pinfunction "C_6") (pintype "passive"))
    )
    (net (code "27") (name "Net-(U2-1Y)") (class "Default")
      (node (ref "C5") (pin "1") (pinfunction "1_1") (pintype "passive"))
      (node (ref "R18") (pin "1") (pinfunction "1_1") (pintype "passive"))
      (node (ref "U2") (pin "4") (pinfunction "1Y_4") (pintype "output"))
      (node (ref "U4") (pin "2") (pinfunction "C_2") (pintype "passive"))
    )
    (net (code "28") (name "Net-(U3-A1)") (class "Default")
      (node (ref "R30") (pin "2") (pinfunction "2_2") (pintype "passive"))
      (node (ref "U3") (pin "3") (pinfunction "A1_3") (pintype "passive"))
    )
    (net (code "29") (name "Net-(U3-A2)") (class "Default")
      (node (ref "R31") (pin "2") (pinfunction "2_2") (pintype "passive"))
      (node (ref "U3") (pin "4") (pinfunction "A2_4") (pintype "passive"))
    )
    (net (code "30") (name "Net-(U3-B1)") (class "Default")
      (node (ref "R5") (pin "1") (pinfunction "1_1") (pintype "passive"))
      (node (ref "R9") (pin "1") (pinfunction "1_1") (pintype "passive"))
      (node (ref "U3") (pin "14") (pinfunction "B1_14") (pintype "passive"))
    )
    (net (code "31") (name "Net-(U3-B2)") (class "Default")
      (node (ref "R11") (pin "1") (pinfunction "1_1") (pintype "passive"))
      (node (ref "R6") (pin "1") (pinfunction "1_1") (pintype "passive"))
      (node (ref "U3") (pin "13") (pinfunction "B2_13") (pintype "passive"))
    )
    (net (code "32") (name "Net-(U3-B3)") (class "Default")
      (node (ref "R14") (pin "1") (pinfunction "1_1") (pintype "passive"))
      (node (ref "U3") (pin "12") (pinfunction "B3_12") (pintype "passive"))
    )
    (net (code "33") (name "Net-(U3-B4)") (class "Default")
      (node (ref "R16") (pin "1") (pinfunction "1_1") (pintype "passive"))
      (node (ref "U3") (pin "11") (pinfunction "B4_11") (pintype "passive"))
    )
    (net (code "34") (name "Net-(U3-NC)") (class "Default")
      (node (ref "R25") (pin "2") (pinfunction "2_2") (pintype "passive"))
      (node (ref "U3") (pin "7") (pinfunction "NC_7") (pintype "passive"))
    )
    (net (code "35") (name "Net-(U3-VDD2)") (class "Default")
      (node (ref "C4") (pin "2") (pinfunction "2_2") (pintype "passive"))
      (node (ref "C7") (pin "1") (pinfunction "1_1") (pintype "passive"))
      (node (ref "R11") (pin "2") (pinfunction "2_2") (pintype "passive"))
      (node (ref "R14") (pin "2") (pinfunction "2_2") (pintype "passive"))
      (node (ref "R16") (pin "2") (pinfunction "2_2") (pintype "passive"))
      (node (ref "R21") (pin "2") (pinfunction "2_2") (pintype "passive"))
      (node (ref "R9") (pin "2") (pinfunction "2_2") (pintype "passive"))
      (node (ref "U3") (pin "16") (pinfunction "VDD2_16") (pintype "passive"))
    )
    (net (code "36") (name "Net-(U6-A1)") (class "Default")
      (node (ref "R1") (pin "1") (pinfunction "1_1") (pintype "passive"))
      (node (ref "R8") (pin "1") (pinfunction "1_1") (pintype "passive"))
      (node (ref "U6") (pin "3") (pinfunction "A1_3") (pintype "passive"))
    )
    (net (code "37") (name "Net-(U6-A2)") (class "Default")
      (node (ref "R10") (pin "1") (pinfunction "1_1") (pintype "passive"))
      (node (ref "R2") (pin "1") (pinfunction "1_1") (pintype "passive"))
      (node (ref "U6") (pin "4") (pinfunction "A2_4") (pintype "passive"))
    )
    (net (code "38") (name "Net-(U6-A3)") (class "Default")
      (node (ref "R13") (pin "1") (pinfunction "1_1") (pintype "passive"))
      (node (ref "R3") (pin "1") (pinfunction "1_1") (pintype "passive"))
      (node (ref "U6") (pin "5") (pinfunction "A3_5") (pintype "passive"))
    )
    (net (code "39") (name "Net-(U6-A4)") (class "Default")
      (node (ref "R15") (pin "1") (pinfunction "1_1") (pintype "passive"))
      (node (ref "R4") (pin "1") (pinfunction "1_1") (pintype "passive"))
      (node (ref "U6") (pin "6") (pinfunction "A4_6") (pintype "passive"))
    )
    (net (code "40") (name "Net-(U6-B1)") (class "Default")
      (node (ref "U6") (pin "14") (pinfunction "B1_14") (pintype "passive"))
      (node (ref "U9") (pin "1") (pinfunction "~{GE}_1") (pintype "input"))
    )
    (net (code "41") (name "Net-(U6-B2)") (class "Default")
      (node (ref "R27") (pin "2") (pinfunction "2_2") (pintype "passive"))
      (node (ref "U6") (pin "13") (pinfunction "B2_13") (pintype "passive"))
    )
    (net (code "42") (name "Net-(U6-B3)") (class "Default")
      (node (ref "R28") (pin "2") (pinfunction "2_2") (pintype "passive"))
      (node (ref "U6") (pin "12") (pinfunction "B3_12") (pintype "passive"))
    )
    (net (code "43") (name "Net-(U6-B4)") (class "Default")
      (node (ref "R29") (pin "2") (pinfunction "2_2") (pintype "passive"))
      (node (ref "U6") (pin "11") (pinfunction "B4_11") (pintype "passive"))
    )
    (net (code "44") (name "Net-(U6-EN2)") (class "Default")
      (node (ref "R24") (pin "2") (pinfunction "2_2") (pintype "passive"))
      (node (ref "U6") (pin "10") (pinfunction "EN2_10") (pintype "passive"))
    )
    (net (code "45") (name "Net-(U6-VDD1)") (class "Default")
      (node (ref "C3") (pin "2") (pinfunction "2_2") (pintype "passive"))
      (node (ref "C6") (pin "1") (pinfunction "1_1") (pintype "passive"))
      (node (ref "R10") (pin "2") (pinfunction "2_2") (pintype "passive"))
      (node (ref "R13") (pin "2") (pinfunction "2_2") (pintype "passive"))
      (node (ref "R15") (pin "2") (pinfunction "2_2") (pintype "passive"))
      (node (ref "R20") (pin "2") (pinfunction "2_2") (pintype "passive"))
      (node (ref "R8") (pin "2") (pinfunction "2_2") (pintype "passive"))
      (node (ref "U6") (pin "1") (pinfunction "VDD1_1") (pintype "passive"))
    )
    (net (code "46") (name "Net-(U7-1Y)") (class "Default")
      (node (ref "R32") (pin "1") (pinfunction "1_1") (pintype "passive"))
      (node (ref "U5") (pin "2") (pinfunction "C_2") (pintype "passive"))
      (node (ref "U7") (pin "4") (pinfunction "1Y_4") (pintype "output"))
      (node (ref "U8") (pin "3") (pinfunction "K_3") (pintype "passive"))
    )
    (net (code "47") (name "Net-(U7-~{GE})") (class "Default")
      (node (ref "R26") (pin "1") (pinfunction "1_1") (pintype "passive"))
      (node (ref "U4") (pin "6") (pinfunction "C_6") (pintype "passive"))
      (node (ref "U7") (pin "1") (pinfunction "~{GE}_1") (pintype "input"))
    )
    (net (code "48") (name "Net-(U8-A)") (class "Default")
      (node (ref "R33") (pin "1") (pinfunction "1_1") (pintype "passive"))
      (node (ref "R34") (pin "2") (pinfunction "2_2") (pintype "passive"))
      (node (ref "U5") (pin "3") (pinfunction "C_3") (pintype "passive"))
      (node (ref "U8") (pin "1") (pinfunction "A_1") (pintype "passive"))
      (node (ref "U8") (pin "2") (pinfunction "NC_2") (pintype "passive"))
    )
    (net (code "49") (name "Net-(U10-+VIN)") (class "Default")
      (node (ref "C15") (pin "2") (pinfunction "2_2") (pintype "passive"))
      (node (ref "C16") (pin "2") (pinfunction "2_2") (pintype "passive"))
      (node (ref "L1") (pin "2") (pinfunction "2_2") (pintype "passive"))
      (node (ref "R37") (pin "1") (pinfunction "1_1") (pintype "passive"))
      (node (ref "U10") (pin "3") (pinfunction "+VIN_3") (pintype "passive"))
    )
    (net (code "50") (name "Net-(U10-+VOUT)") (class "Default")
      (node (ref "L2") (pin "1") (pinfunction "1_1") (pintype "passive"))
      (node (ref "R38") (pin "2") (pinfunction "2_2") (pintype "passive"))
      (node (ref "U10") (pin "8") (pinfunction "+VOUT_8") (pintype "passive"))
    )
    (net (code "51") (name "VDD_H") (class "Default")
      (node (ref "C1") (pin "1") (pinfunction "1_1") (pintype "passive"))
      (node (ref "C2") (pin "1") (pinfunction "1_1") (pintype "passive"))
      (node (ref "R17") (pin "1") (pinfunction "1_1") (pintype "passive"))
      (node (ref "R18") (pin "2") (pinfunction "2_2") (pintype "passive"))
      (node (ref "R20") (pin "1") (pinfunction "1_1") (pintype "passive"))
      (node (ref "R21") (pin "1") (pinfunction "1_1") (pintype "passive"))
      (node (ref "R39") (pin "2") (pinfunction "2_2") (pintype "passive"))
      (node (ref "R7") (pin "2") (pinfunction "2_2") (pintype "passive"))
      (node (ref "TP2") (pin "1") (pinfunction "1_1") (pintype "passive"))
      (node (ref "U1") (pin "5") (pinfunction "VCC_5") (pintype "power_in"))
      (node (ref "U2") (pin "5") (pinfunction "VCC_5") (pintype "power_in"))
      (node (ref "U5") (pin "8") (pinfunction "C_8") (pintype "passive"))
      (node (ref "X1") (pin "2") (pinfunction "2_2") (pintype "passive"))
    )
    (net (code "52") (name "VDD_H_EXT") (class "Default")
      (node (ref "J1") (pin "1") (pinfunction "1_1") (pintype "passive"))
      (node (ref "J1") (pin "2") (pinfunction "2_2") (pintype "passive"))
      (node (ref "X1") (pin "1") (pinfunction "1_1") (pintype "passive"))
    )
    (net (code "53") (name "VDD_T") (class "Default")
      (node (ref "C10") (pin "1") (pinfunction "1_1") (pintype "passive"))
      (node (ref "C11") (pin "1") (pinfunction "1_1") (pintype "passive"))
      (node (ref "C12") (pin "1") (pinfunction "1_1") (pintype "passive"))
      (node (ref "C13") (pin "2") (pinfunction "2_2") (pintype "passive"))
      (node (ref "C8") (pin "2") (pinfunction "2_2") (pintype "passive"))
      (node (ref "C9") (pin "2") (pinfunction "2_2") (pintype "passive"))
      (node (ref "D1") (pin "1") (pintype "passive"))
      (node (ref "D1") (pin "2") (pintype "passive"))
      (node (ref "J2") (pin "1") (pinfunction "1_1") (pintype "passive"))
      (node (ref "J2") (pin "2") (pinfunction "2_2") (pintype "passive"))
      (node (ref "L1") (pin "1") (pinfunction "1_1") (pintype "passive"))
      (node (ref "R24") (pin "1") (pinfunction "1_1") (pintype "passive"))
      (node (ref "R25") (pin "1") (pinfunction "1_1") (pintype "passive"))
      (node (ref "R26") (pin "2") (pinfunction "2_2") (pintype "passive"))
      (node (ref "R32") (pin "2") (pinfunction "2_2") (pintype "passive"))
      (node (ref "R33") (pin "2") (pinfunction "2_2") (pintype "passive"))
      (node (ref "R35") (pin "2") (pinfunction "2_2") (pintype "passive"))
      (node (ref "R36") (pin "2") (pinfunction "2_2") (pintype "passive"))
      (node (ref "R37") (pin "2") (pinfunction "2_2") (pintype "passive"))
      (node (ref "TP4") (pin "1") (pinfunction "1_1") (pintype "passive"))
      (node (ref "U3") (pin "1") (pinfunction "VDD1_1") (pintype "passive"))
      (node (ref "U4") (pin "8") (pinfunction "C_8") (pintype "passive"))
      (node (ref "U6") (pin "16") (pinfunction "VDD2_16") (pintype "passive"))
      (node (ref "U7") (pin "5") (pinfunction "VCC_5") (pintype "power_in"))
      (node (ref "U9") (pin "5") (pinfunction "VCC_5") (pintype "power_in"))
    )
    (net (code "54") (name "unconnected-(U3-A3-Pad5)") (class "Default")
      (node (ref "U3") (pin "5") (pinfunction "A3_5") (pintype "passive"))
    )
    (net (code "55") (name "unconnected-(U3-A4-Pad6)") (class "Default")
      (node (ref "U3") (pin "6") (pinfunction "A4_6") (pintype "passive"))
    )
    (net (code "56") (name "unconnected-(U3-EN2-Pad10)") (class "Default")
      (node (ref "U3") (pin "10") (pinfunction "EN2_10") (pintype "passive"))
    )
    (net (code "57") (name "unconnected-(U4-NC-Pad1)") (class "Default")
      (node (ref "U4") (pin "1") (pinfunction "NC_1") (pintype "passive"))
    )
    (net (code "58") (name "unconnected-(U4-NC-Pad4)") (class "Default")
      (node (ref "U4") (pin "4") (pinfunction "NC_4") (pintype "passive"))
    )
    (net (code "59") (name "unconnected-(U5-NC-Pad1)") (class "Default")
      (node (ref "U5") (pin "1") (pinfunction "NC_1") (pintype "passive"))
    )
    (net (code "60") (name "unconnected-(U5-NC-Pad4)") (class "Default")
      (node (ref "U5") (pin "4") (pinfunction "NC_4") (pintype "passive"))
    )
    (net (code "61") (name "unconnected-(U6-NC-Pad7)") (class "Default")
      (node (ref "U6") (pin "7") (pinfunction "NC_7") (pintype "passive"))
    )
    (net (code "62") (name "unconnected-(U10-NA-Pad10)") (class "Default")
      (node (ref "U10") (pin "10") (pinfunction "NA_10") (pintype "passive"))
    )
    (net (code "63") (name "unconnected-(U10-NA-Pad12)") (class "Default")
      (node (ref "U10") (pin "12") (pinfunction "NA_12") (pintype "passive"))
    )
    (net (code "64") (name "unconnected-(U10-NA-Pad14)") (class "Default")
      (node (ref "U10") (pin "14") (pinfunction "NA_14") (pintype "passive"))
    )
    (net (code "65") (name "unconnected-(U10-NC-Pad5)") (class "Default")
      (node (ref "U10") (pin "5") (pinfunction "NC_5") (pintype "passive"))
    )
  )
)
